# isp_atmega40pin.net
KiCad netlist of a schematic drawn in EAGLE
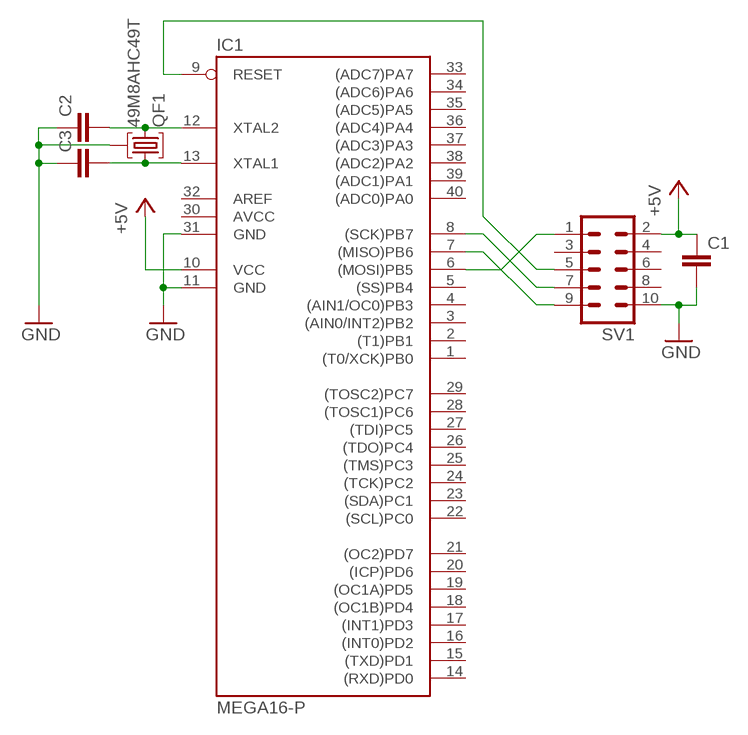
[diagram p0: schematic, sheet 1]

(export (version "E")
  (design (tool "Eeschema 10.0.6"))
  (components
    (comp (ref "C1")
      (value "C-EU025-025X050")
      (footprint "eagle-import:C025-025X050")
      (libsource (lib "eagle-import") (part "C-EU025-025X050"))
    )
    (comp (ref "C2")
      (value "C-EU025-025X050")
      (footprint "eagle-import:C025-025X050")
      (libsource (lib "eagle-import") (part "C-EU025-025X050"))
    )
    (comp (ref "C3")
      (value "C-EU025-025X050")
      (footprint "eagle-import:C025-025X050")
      (libsource (lib "eagle-import") (part "C-EU025-025X050"))
    )
    (comp (ref "IC1")
      (value "MEGA16-P")
      (footprint "eagle-import:DIL40")
      (fields (field (name "MPN") "ATMEGA16-16PU"))
      (libsource (lib "eagle-import") (part "MEGA16-P"))
    )
    (comp (ref "QF1")
      (value "49M8AHC49T")
      (footprint "eagle-import:HC49U")
      (libsource (lib "eagle-import") (part "49M8AHC49T"))
    )
    (comp (ref "SV1")
      (value "ML10")
      (footprint "eagle-import:ML10")
      (libsource (lib "eagle-import") (part "ML10"))
    )
  )
  (nets
    (net (code "1") (name "+5V") (class "Default")
      (node (ref "C1") (pin "1") (pinfunction "1_1") (pintype "passive"))
      (node (ref "IC1") (pin "10") (pinfunction "VCC_10") (pintype "power_in"))
      (node (ref "SV1") (pin "2") (pinfunction "2_2") (pintype "passive"))
    )
    (net (code "2") (name "/AVCC") (class "Default")
      (node (ref "IC1") (pin "30") (pinfunction "AVCC_30") (pintype "power_in"))
    )
    (net (code "3") (name "GND") (class "Default")
      (node (ref "C1") (pin "2") (pinfunction "2_2") (pintype "passive"))
      (node (ref "C2") (pin "1") (pinfunction "1_1") (pintype "passive"))
      (node (ref "C3") (pin "1") (pinfunction "1_1") (pintype "passive"))
      (node (ref "IC1") (pin "11") (pinfunction "GND_11") (pintype "power_in"))
      (node (ref "IC1") (pin "31") (pinfunction "GND_31") (pintype "power_in"))
      (node (ref "QF1") (pin "2") (pinfunction "2_2") (pintype "passive"))
      (node (ref "SV1") (pin "10") (pinfunction "10_10") (pintype "passive"))
    )
    (net (code "4") (name "Net-(IC1-(MISO)PB6)") (class "Default")
      (node (ref "IC1") (pin "7") (pinfunction "(MISO)PB6_7") (pintype "bidirectional"))
      (node (ref "SV1") (pin "9") (pinfunction "9_9") (pintype "passive"))
    )
    (net (code "5") (name "Net-(IC1-(MOSI)PB5)") (class "Default")
      (node (ref "IC1") (pin "6") (pinfunction "(MOSI)PB5_6") (pintype "bidirectional"))
      (node (ref "SV1") (pin "1") (pinfunction "1_1") (pintype "passive"))
    )
    (net (code "6") (name "Net-(IC1-(SCK)PB7)") (class "Default")
      (node (ref "IC1") (pin "8") (pinfunction "(SCK)PB7_8") (pintype "bidirectional"))
      (node (ref "SV1") (pin "7") (pinfunction "7_7") (pintype "passive"))
    )
    (net (code "7") (name "Net-(IC1-RESET)") (class "Default")
      (node (ref "IC1") (pin "9") (pinfunction "RESET_9") (pintype "input"))
      (node (ref "SV1") (pin "5") (pinfunction "5_5") (pintype "passive"))
    )
    (net (code "8") (name "Net-(IC1-XTAL1)") (class "Default")
      (node (ref "C3") (pin "2") (pinfunction "2_2") (pintype "passive"))
      (node (ref "IC1") (pin "13") (pinfunction "XTAL1_13") (pintype "bidirectional"))
      (node (ref "QF1") (pin "1") (pinfunction "1_1") (pintype "passive"))
    )
    (net (code "9") (name "Net-(IC1-XTAL2)") (class "Default")
      (node (ref "C2") (pin "2") (pinfunction "2_2") (pintype "passive"))
      (node (ref "IC1") (pin "12") (pinfunction "XTAL2_12") (pintype "bidirectional"))
      (node (ref "QF1") (pin "3") (pinfunction "3_3") (pintype "passive"))
    )
    (net (code "10") (name "unconnected-(IC1-(ADC0)PA0-Pad40)") (class "Default")
      (node (ref "IC1") (pin "40") (pinfunction "(ADC0)PA0_40") (pintype "bidirectional"))
    )
    (net (code "11") (name "unconnected-(IC1-(ADC1)PA1-Pad39)") (class "Default")
      (node (ref "IC1") (pin "39") (pinfunction "(ADC1)PA1_39") (pintype "bidirectional"))
    )
    (net (code "12") (name "unconnected-(IC1-(ADC2)PA2-Pad38)") (class "Default")
      (node (ref "IC1") (pin "38") (pinfunction "(ADC2)PA2_38") (pintype "bidirectional"))
    )
    (net (code "13") (name "unconnected-(IC1-(ADC3)PA3-Pad37)") (class "Default")
      (node (ref "IC1") (pin "37") (pinfunction "(ADC3)PA3_37") (pintype "bidirectional"))
    )
    (net (code "14") (name "unconnected-(IC1-(ADC4)PA4-Pad36)") (class "Default")
      (node (ref "IC1") (pin "36") (pinfunction "(ADC4)PA4_36") (pintype "bidirectional"))
    )
    (net (code "15") (name "unconnected-(IC1-(ADC5)PA5-Pad35)") (class "Default")
      (node (ref "IC1") (pin "35") (pinfunction "(ADC5)PA5_35") (pintype "bidirectional"))
    )
    (net (code "16") (name "unconnected-(IC1-(ADC6)PA6-Pad34)") (class "Default")
      (node (ref "IC1") (pin "34") (pinfunction "(ADC6)PA6_34") (pintype "bidirectional"))
    )
    (net (code "17") (name "unconnected-(IC1-(ADC7)PA7-Pad33)") (class "Default")
      (node (ref "IC1") (pin "33") (pinfunction "(ADC7)PA7_33") (pintype "bidirectional"))
    )
    (net (code "18") (name "unconnected-(IC1-(AIN0{slash}INT2)PB2-Pad3)") (class "Default")
      (node (ref "IC1") (pin "3") (pinfunction "(AIN0/INT2)PB2_3") (pintype "bidirectional"))
    )
    (net (code "19") (name "unconnected-(IC1-(AIN1{slash}OC0)PB3-Pad4)") (class "Default")
      (node (ref "IC1") (pin "4") (pinfunction "(AIN1/OC0)PB3_4") (pintype "bidirectional"))
    )
    (net (code "20") (name "unconnected-(IC1-(ICP)PD6-Pad20)") (class "Default")
      (node (ref "IC1") (pin "20") (pinfunction "(ICP)PD6_20") (pintype "bidirectional"))
    )
    (net (code "21") (name "unconnected-(IC1-(INT0)PD2-Pad16)") (class "Default")
      (node (ref "IC1") (pin "16") (pinfunction "(INT0)PD2_16") (pintype "bidirectional"))
    )
    (net (code "22") (name "unconnected-(IC1-(INT1)PD3-Pad17)") (class "Default")
      (node (ref "IC1") (pin "17") (pinfunction "(INT1)PD3_17") (pintype "bidirectional"))
    )
    (net (code "23") (name "unconnected-(IC1-(OC1A)PD5-Pad19)") (class "Default")
      (node (ref "IC1") (pin "19") (pinfunction "(OC1A)PD5_19") (pintype "bidirectional"))
    )
    (net (code "24") (name "unconnected-(IC1-(OC1B)PD4-Pad18)") (class "Default")
      (node (ref "IC1") (pin "18") (pinfunction "(OC1B)PD4_18") (pintype "bidirectional"))
    )
    (net (code "25") (name "unconnected-(IC1-(OC2)PD7-Pad21)") (class "Default")
      (node (ref "IC1") (pin "21") (pinfunction "(OC2)PD7_21") (pintype "bidirectional"))
    )
    (net (code "26") (name "unconnected-(IC1-(RXD)PD0-Pad14)") (class "Default")
      (node (ref "IC1") (pin "14") (pinfunction "(RXD)PD0_14") (pintype "bidirectional"))
    )
    (net (code "27") (name "unconnected-(IC1-(SCL)PC0-Pad22)") (class "Default")
      (node (ref "IC1") (pin "22") (pinfunction "(SCL)PC0_22") (pintype "bidirectional"))
    )
    (net (code "28") (name "unconnected-(IC1-(SDA)PC1-Pad23)") (class "Default")
      (node (ref "IC1") (pin "23") (pinfunction "(SDA)PC1_23") (pintype "bidirectional"))
    )
    (net (code "29") (name "unconnected-(IC1-(SS)PB4-Pad5)") (class "Default")
      (node (ref "IC1") (pin "5") (pinfunction "(SS)PB4_5") (pintype "bidirectional"))
    )
    (net (code "30") (name "unconnected-(IC1-(T0{slash}XCK)PB0-Pad1)") (class "Default")
      (node (ref "IC1") (pin "1") (pinfunction "(T0/XCK)PB0_1") (pintype "bidirectional"))
    )
    (net (code "31") (name "unconnected-(IC1-(T1)PB1-Pad2)") (class "Default")
      (node (ref "IC1") (pin "2") (pinfunction "(T1)PB1_2") (pintype "bidirectional"))
    )
    (net (code "32") (name "unconnected-(IC1-(TCK)PC2-Pad24)") (class "Default")
      (node (ref "IC1") (pin "24") (pinfunction "(TCK)PC2_24") (pintype "bidirectional"))
    )
    (net (code "33") (name "unconnected-(IC1-(TDI)PC5-Pad27)") (class "Default")
      (node (ref "IC1") (pin "27") (pinfunction "(TDI)PC5_27") (pintype "bidirectional"))
    )
    (net (code "34") (name "unconnected-(IC1-(TDO)PC4-Pad26)") (class "Default")
      (node (ref "IC1") (pin "26") (pinfunction "(TDO)PC4_26") (pintype "bidirectional"))
    )
    (net (code "35") (name "unconnected-(IC1-(TMS)PC3-Pad25)") (class "Default")
      (node (ref "IC1") (pin "25") (pinfunction "(TMS)PC3_25") (pintype "bidirectional"))
    )
    (net (code "36") (name "unconnected-(IC1-(TOSC1)PC6-Pad28)") (class "Default")
      (node (ref "IC1") (pin "28") (pinfunction "(TOSC1)PC6_28") (pintype "bidirectional"))
    )
    (net (code "37") (name "unconnected-(IC1-(TOSC2)PC7-Pad29)") (class "Default")
      (node (ref "IC1") (pin "29") (pinfunction "(TOSC2)PC7_29") (pintype "bidirectional"))
    )
    (net (code "38") (name "unconnected-(IC1-(TXD)PD1-Pad15)") (class "Default")
      (node (ref "IC1") (pin "15") (pinfunction "(TXD)PD1_15") (pintype "bidirectional"))
    )
    (net (code "39") (name "unconnected-(IC1-AREF-Pad32)") (class "Default")
      (node (ref "IC1") (pin "32") (pinfunction "AREF_32") (pintype "passive"))
    )
    (net (code "40") (name "unconnected-(SV1-Pad3)") (class "Default")
      (node (ref "SV1") (pin "3") (pinfunction "3_3") (pintype "passive"))
    )
    (net (code "41") (name "unconnected-(SV1-Pad4)") (class "Default")
      (node (ref "SV1") (pin "4") (pinfunction "4_4") (pintype "passive"))
    )
    (net (code "42") (name "unconnected-(SV1-Pad6)") (class "Default")
      (node (ref "SV1") (pin "6") (pinfunction "6_6") (pintype "passive"))
    )
    (net (code "43") (name "unconnected-(SV1-Pad8)") (class "Default")
      (node (ref "SV1") (pin "8") (pinfunction "8_8") (pintype "passive"))
    )
  )
)
